# bloodhound_gprs_0_alph.net
KiCad netlist of a schematic drawn in Altium Designer
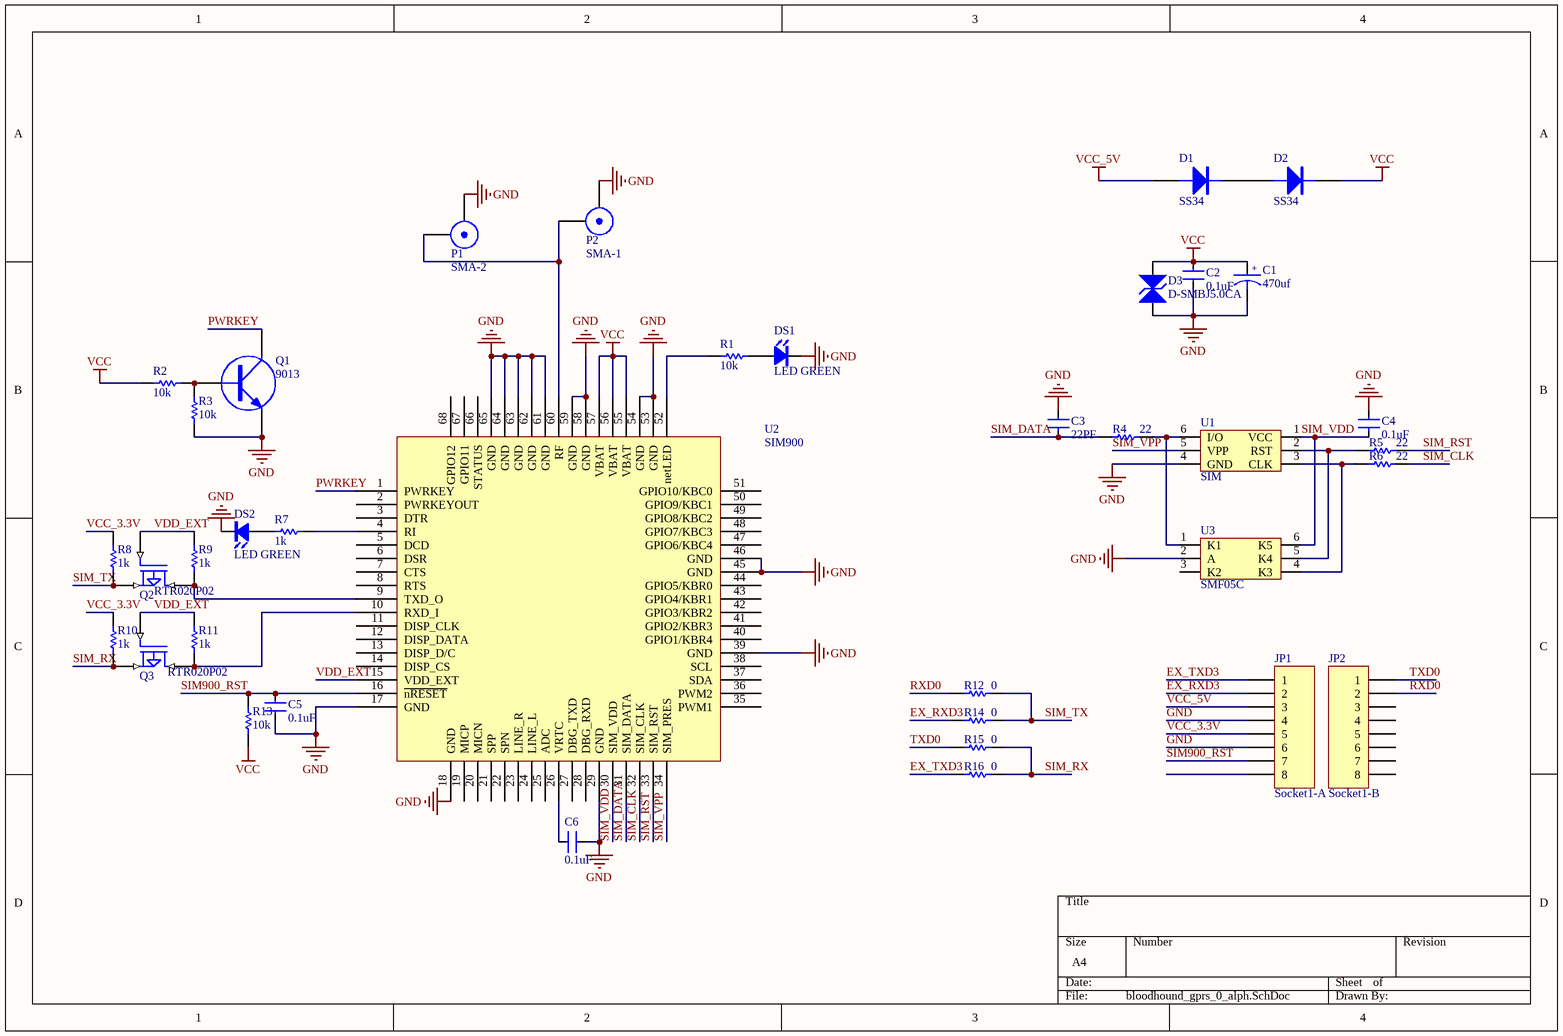
[diagram p0: bloodhound_gprs_0_alph.SchDoc]

(export (version "E")
  (design (tool "Eeschema 10.0.6"))
  (components
    (comp (ref "C1")
      (value "470uf")
      (footprint "C6032")
      (description "钽电容")
      (libsource (lib "BH_DESIGN_DEVICE") (part "CAP-T"))
    )
    (comp (ref "C2")
      (value "0.1uF")
      (footprint "C0603")
      (description "SMD-CAP")
      (libsource (lib "BH_DESIGN_DEVICE") (part "CAP-SMD"))
    )
    (comp (ref "C3")
      (value "22PF")
      (footprint "C0603")
      (description "SMD-CAP")
      (libsource (lib "BH_DESIGN_DEVICE") (part "CAP-SMD"))
    )
    (comp (ref "C4")
      (value "0.1uF")
      (footprint "C0603")
      (description "SMD-CAP")
      (libsource (lib "BH_DESIGN_DEVICE") (part "CAP-SMD"))
    )
    (comp (ref "C5")
      (value "0.1uF")
      (footprint "C0603")
      (description "SMD-CAP")
      (libsource (lib "BH_DESIGN_DEVICE") (part "CAP-SMD"))
    )
    (comp (ref "C6")
      (value "0.1uF")
      (footprint "C0603")
      (description "SMD-CAP")
      (libsource (lib "BH_DESIGN_DEVICE") (part "CAP-SMD"))
    )
    (comp (ref "D1")
      (value "SS34")
      (footprint "DO-214")
      (description "Diode")
      (libsource (lib "BH_DESIGN_DEVICE") (part "DIODE"))
    )
    (comp (ref "D2")
      (value "SS34")
      (footprint "DO-214")
      (description "Diode")
      (libsource (lib "BH_DESIGN_DEVICE") (part "DIODE"))
    )
    (comp (ref "D3")
      (value "D-SMBJ5.0CA")
      (footprint "DO-214")
      (description "TVS")
      (libsource (lib "BH_DESIGN_DEVICE") (part "D-SMBJ5.0CA"))
    )
    (comp (ref "DS1") (value "LED GREEN") (footprint "D0805") (libsource (lib "") (part "LED_1")))
    (comp (ref "DS2")
      (value "LED GREEN")
      (footprint "D0805")
      (libsource (lib "BH_DESIGN_DEVICE") (part "LED"))
    )
    (comp (ref "JP1")
      (value "Socket1-A")
      (footprint "SIP1x8x2.54")
      (description "2.0排针")
      (libsource (lib "5D_CONNECTOR") (part "SIP1X8"))
    )
    (comp (ref "JP2")
      (value "Socket1-B")
      (footprint "SIP1x8x2.54")
      (description "2.0排针")
      (libsource (lib "") (part "SIP1X8_1"))
    )
    (comp (ref "P1")
      (value "SMA-2")
      (footprint "IPX")
      (description "IPX")
      (libsource (lib "BH_DESIGN_CONNECTOR") (part "BNC"))
    )
    (comp (ref "P2")
      (value "SMA-1")
      (footprint "SMA-2")
      (description "SMB-KWE")
      (libsource (lib "") (part "BNC_1"))
    )
    (comp (ref "Q1")
      (value "9013")
      (footprint "SOT23-3L")
      (description "NPN Transistor")
      (libsource (lib "BH_DESIGN_DEVICE") (part "NPN"))
    )
    (comp (ref "Q2")
      (value "RTR020P02")
      (footprint "TSMT3")
      (description "P MOSFET")
      (libsource (lib "BH_DESIGN_DEVICE") (part "MOSFET P"))
    )
    (comp (ref "Q3")
      (value "RTR020P02")
      (footprint "TSMT3")
      (description "P MOSFET")
      (libsource (lib "BH_DESIGN_DEVICE") (part "MOSFET P"))
    )
    (comp (ref "R1")
      (value "10k")
      (footprint "R0603")
      (description "Resistor")
      (libsource (lib "BH_DESIGN_DEVICE") (part "RES"))
    )
    (comp (ref "R2")
      (value "10k")
      (footprint "R0603")
      (description "Resistor")
      (libsource (lib "BH_DESIGN_DEVICE") (part "RES"))
    )
    (comp (ref "R3")
      (value "10k")
      (footprint "R0603")
      (description "Resistor")
      (libsource (lib "BH_DESIGN_DEVICE") (part "RES"))
    )
    (comp (ref "R4")
      (value "22")
      (footprint "R0603")
      (description "Resistor")
      (libsource (lib "BH_DESIGN_DEVICE") (part "RES"))
    )
    (comp (ref "R5")
      (value "22")
      (footprint "R0603")
      (description "Resistor")
      (libsource (lib "BH_DESIGN_DEVICE") (part "RES"))
    )
    (comp (ref "R6")
      (value "22")
      (footprint "R0603")
      (description "Resistor")
      (libsource (lib "BH_DESIGN_DEVICE") (part "RES"))
    )
    (comp (ref "R7")
      (value "1k")
      (footprint "R0603")
      (description "Resistor")
      (libsource (lib "BH_DESIGN_DEVICE") (part "RES"))
    )
    (comp (ref "R8")
      (value "1k")
      (footprint "R0603")
      (description "Resistor")
      (libsource (lib "BH_DESIGN_DEVICE") (part "RES"))
    )
    (comp (ref "R9")
      (value "1k")
      (footprint "R0603")
      (description "Resistor")
      (libsource (lib "BH_DESIGN_DEVICE") (part "RES"))
    )
    (comp (ref "R10")
      (value "1k")
      (footprint "R0603")
      (description "Resistor")
      (libsource (lib "BH_DESIGN_DEVICE") (part "RES"))
    )
    (comp (ref "R11")
      (value "1k")
      (footprint "R0603")
      (description "Resistor")
      (libsource (lib "BH_DESIGN_DEVICE") (part "RES"))
    )
    (comp (ref "R12")
      (value "0")
      (footprint "R0603")
      (description "Resistor")
      (libsource (lib "BH_DESIGN_DEVICE") (part "RES"))
    )
    (comp (ref "R13")
      (value "10k")
      (footprint "R0603")
      (description "Resistor")
      (libsource (lib "BH_DESIGN_DEVICE") (part "RES"))
    )
    (comp (ref "R14")
      (value "0")
      (footprint "R0603")
      (description "Resistor")
      (libsource (lib "BH_DESIGN_DEVICE") (part "RES"))
    )
    (comp (ref "R15")
      (value "0")
      (footprint "R0603")
      (description "Resistor")
      (libsource (lib "BH_DESIGN_DEVICE") (part "RES"))
    )
    (comp (ref "R16")
      (value "0")
      (footprint "R0603")
      (description "Resistor")
      (libsource (lib "BH_DESIGN_DEVICE") (part "RES"))
    )
    (comp (ref "U1")
      (value "SIM")
      (footprint "SIM")
      (description "手机SIM卡")
      (libsource (lib "BH_DESIGN_CONNECTOR") (part "SIM"))
    )
    (comp (ref "U2")
      (value "SIM900")
      (footprint "GSM_900A")
      (libsource (lib "BH_DESIGN_DEVICE") (part "SIM900"))
    )
    (comp (ref "U3")
      (value "SMF05C")
      (footprint "SOT-363")
      (description "TVS")
      (libsource (lib "SIM900_MD") (part "SMF05C"))
    )
  )
  (nets
    (net (code "1") (name "/EX_RXD3") (class "Default")
      (node (ref "JP1") (pin "2") (pinfunction "2_2") (pintype "passive"))
      (node (ref "R14") (pin "2") (pinfunction "2_2") (pintype "passive"))
    )
    (net (code "2") (name "/EX_TXD3") (class "Default")
      (node (ref "JP1") (pin "1") (pinfunction "1_1") (pintype "passive"))
      (node (ref "R16") (pin "2") (pinfunction "2_2") (pintype "passive"))
    )
    (net (code "3") (name "/PWRKEY") (class "Default")
      (node (ref "Q1") (pin "C") (pinfunction "C_C") (pintype "passive"))
      (node (ref "U2") (pin "1") (pinfunction "PWRKEY_1") (pintype "passive"))
    )
    (net (code "4") (name "/RXD0") (class "Default")
      (node (ref "JP2") (pin "2") (pinfunction "2_2") (pintype "passive"))
      (node (ref "R12") (pin "2") (pinfunction "2_2") (pintype "passive"))
    )
    (net (code "5") (name "/SIM900_RST") (class "Default")
      (node (ref "C5") (pin "1") (pinfunction "1_1") (pintype "passive"))
      (node (ref "JP1") (pin "7") (pinfunction "7_7") (pintype "passive"))
      (node (ref "R13") (pin "1") (pinfunction "1_1") (pintype "passive"))
      (node (ref "U2") (pin "16") (pinfunction "~{nRESET}_16") (pintype "passive"))
    )
    (net (code "6") (name "/SIM_CLK") (class "Default")
      (node (ref "R6") (pin "1") (pinfunction "1_1") (pintype "passive"))
      (node (ref "U2") (pin "32") (pinfunction "SIM_CLK_32") (pintype "passive"))
    )
    (net (code "7") (name "/SIM_DATA") (class "Default")
      (node (ref "C3") (pin "1") (pinfunction "1_1") (pintype "passive"))
      (node (ref "R4") (pin "2") (pinfunction "2_2") (pintype "passive"))
      (node (ref "U2") (pin "31") (pinfunction "SIM_DATA_31") (pintype "passive"))
    )
    (net (code "8") (name "/SIM_RST") (class "Default")
      (node (ref "R5") (pin "1") (pinfunction "1_1") (pintype "passive"))
      (node (ref "U2") (pin "33") (pinfunction "SIM_RST_33") (pintype "passive"))
    )
    (net (code "9") (name "/SIM_RX") (class "Default")
      (node (ref "Q3") (pin "3") (pinfunction "S_3") (pintype "input"))
      (node (ref "R10") (pin "2") (pinfunction "2_2") (pintype "passive"))
      (node (ref "R15") (pin "1") (pinfunction "1_1") (pintype "passive"))
      (node (ref "R16") (pin "1") (pinfunction "1_1") (pintype "passive"))
    )
    (net (code "10") (name "/SIM_TX") (class "Default")
      (node (ref "Q2") (pin "3") (pinfunction "S_3") (pintype "input"))
      (node (ref "R12") (pin "1") (pinfunction "1_1") (pintype "passive"))
      (node (ref "R14") (pin "1") (pinfunction "1_1") (pintype "passive"))
      (node (ref "R8") (pin "2") (pinfunction "2_2") (pintype "passive"))
    )
    (net (code "11") (name "/SIM_VDD") (class "Default")
      (node (ref "C4") (pin "1") (pinfunction "1_1") (pintype "passive"))
      (node (ref "U1") (pin "1") (pinfunction "VCC_1") (pintype "passive"))
      (node (ref "U2") (pin "30") (pinfunction "SIM_VDD_30") (pintype "passive"))
      (node (ref "U3") (pin "6") (pinfunction "K5_6") (pintype "passive"))
    )
    (net (code "12") (name "/SIM_VPP") (class "Default")
      (node (ref "U1") (pin "5") (pinfunction "VPP_5") (pintype "passive"))
      (node (ref "U2") (pin "34") (pinfunction "SIM_PRES_34") (pintype "passive"))
    )
    (net (code "13") (name "/TXD0") (class "Default")
      (node (ref "JP2") (pin "1") (pinfunction "1_1") (pintype "passive"))
      (node (ref "R15") (pin "2") (pinfunction "2_2") (pintype "passive"))
    )
    (net (code "14") (name "/VCC_3.3V") (class "Default")
      (node (ref "JP1") (pin "5") (pinfunction "5_5") (pintype "passive"))
      (node (ref "R10") (pin "1") (pinfunction "1_1") (pintype "passive"))
      (node (ref "R8") (pin "1") (pinfunction "1_1") (pintype "passive"))
    )
    (net (code "15") (name "/VDD_EXT") (class "Default")
      (node (ref "Q2") (pin "1") (pinfunction "G_1") (pintype "input"))
      (node (ref "Q3") (pin "1") (pinfunction "G_1") (pintype "input"))
      (node (ref "R11") (pin "1") (pinfunction "1_1") (pintype "passive"))
      (node (ref "R9") (pin "1") (pinfunction "1_1") (pintype "passive"))
      (node (ref "U2") (pin "15") (pinfunction "VDD_EXT_15") (pintype "passive"))
    )
    (net (code "16") (name "GND") (class "Default")
      (node (ref "C1") (pin "2") (pinfunction "2_2") (pintype "passive"))
      (node (ref "C2") (pin "1") (pinfunction "1_1") (pintype "passive"))
      (node (ref "C3") (pin "2") (pinfunction "2_2") (pintype "passive"))
      (node (ref "C4") (pin "2") (pinfunction "2_2") (pintype "passive"))
      (node (ref "C5") (pin "2") (pinfunction "2_2") (pintype "passive"))
      (node (ref "C6") (pin "2") (pinfunction "2_2") (pintype "passive"))
      (node (ref "D3") (pin "A") (pinfunction "1_A") (pintype "passive"))
      (node (ref "DS1") (pin "K") (pinfunction "2_K") (pintype "passive"))
      (node (ref "DS2") (pin "K") (pinfunction "2_K") (pintype "passive"))
      (node (ref "JP1") (pin "4") (pinfunction "4_4") (pintype "passive"))
      (node (ref "JP1") (pin "6") (pinfunction "6_6") (pintype "passive"))
      (node (ref "P1") (pin "2") (pinfunction "Y_2") (pintype "passive"))
      (node (ref "P2") (pin "2") (pinfunction "Y_2") (pintype "passive"))
      (node (ref "Q1") (pin "E") (pinfunction "E_E") (pintype "passive"))
      (node (ref "R3") (pin "1") (pinfunction "1_1") (pintype "passive"))
      (node (ref "U1") (pin "4") (pinfunction "GND_4") (pintype "passive"))
      (node (ref "U2") (pin "17") (pinfunction "GND_17") (pintype "passive"))
      (node (ref "U2") (pin "18") (pinfunction "GND_18") (pintype "passive"))
      (node (ref "U2") (pin "29") (pinfunction "GND_29") (pintype "passive"))
      (node (ref "U2") (pin "39") (pinfunction "GND_39") (pintype "passive"))
      (node (ref "U2") (pin "45") (pinfunction "GND_45") (pintype "passive"))
      (node (ref "U2") (pin "46") (pinfunction "GND_46") (pintype "passive"))
      (node (ref "U2") (pin "53") (pinfunction "GND_53") (pintype "passive"))
      (node (ref "U2") (pin "54") (pinfunction "GND_54") (pintype "passive"))
      (node (ref "U2") (pin "58") (pinfunction "GND_58") (pintype "passive"))
      (node (ref "U2") (pin "59") (pinfunction "GND_59") (pintype "passive"))
      (node (ref "U2") (pin "61") (pinfunction "GND_61") (pintype "passive"))
      (node (ref "U2") (pin "62") (pinfunction "GND_62") (pintype "passive"))
      (node (ref "U2") (pin "63") (pinfunction "GND_63") (pintype "passive"))
      (node (ref "U2") (pin "64") (pinfunction "GND_64") (pintype "passive"))
      (node (ref "U2") (pin "65") (pinfunction "GND_65") (pintype "passive"))
      (node (ref "U3") (pin "2") (pinfunction "A_2") (pintype "passive"))
    )
    (net (code "17") (name "Net-(D1-K)") (class "Default")
      (node (ref "D1") (pin "2") (pinfunction "K_2") (pintype "passive"))
      (node (ref "D2") (pin "1") (pinfunction "A_1") (pintype "passive"))
    )
    (net (code "18") (name "Net-(DS1-1)") (class "Default")
      (node (ref "DS1") (pin "A") (pinfunction "1_A") (pintype "passive"))
      (node (ref "R1") (pin "1") (pinfunction "1_1") (pintype "passive"))
    )
    (net (code "19") (name "Net-(DS2-1)") (class "Default")
      (node (ref "DS2") (pin "A") (pinfunction "1_A") (pintype "passive"))
      (node (ref "R7") (pin "1") (pinfunction "1_1") (pintype "passive"))
    )
    (net (code "20") (name "Net-(P1-X)") (class "Default")
      (node (ref "P1") (pin "1") (pinfunction "X_1") (pintype "passive"))
      (node (ref "P2") (pin "1") (pinfunction "X_1") (pintype "passive"))
      (node (ref "U2") (pin "60") (pinfunction "RF_60") (pintype "passive"))
    )
    (net (code "21") (name "Net-(Q1-PadB)") (class "Default")
      (node (ref "Q1") (pin "B") (pinfunction "B_B") (pintype "passive"))
      (node (ref "R2") (pin "2") (pinfunction "2_2") (pintype "passive"))
      (node (ref "R3") (pin "2") (pinfunction "2_2") (pintype "passive"))
    )
    (net (code "22") (name "Net-(Q2-D)") (class "Default")
      (node (ref "Q2") (pin "2") (pinfunction "D_2") (pintype "input"))
      (node (ref "R9") (pin "2") (pinfunction "2_2") (pintype "passive"))
      (node (ref "U2") (pin "9") (pinfunction "TXD_O_9") (pintype "passive"))
    )
    (net (code "23") (name "Net-(Q3-D)") (class "Default")
      (node (ref "Q3") (pin "2") (pinfunction "D_2") (pintype "input"))
      (node (ref "R11") (pin "2") (pinfunction "2_2") (pintype "passive"))
      (node (ref "U2") (pin "10") (pinfunction "RXD_I_10") (pintype "passive"))
    )
    (net (code "24") (name "Net-(U1-CLK)") (class "Default")
      (node (ref "R6") (pin "2") (pinfunction "2_2") (pintype "passive"))
      (node (ref "U1") (pin "3") (pinfunction "CLK_3") (pintype "passive"))
      (node (ref "U3") (pin "4") (pinfunction "K3_4") (pintype "passive"))
    )
    (net (code "25") (name "Net-(U1-I{slash}O)") (class "Default")
      (node (ref "R4") (pin "1") (pinfunction "1_1") (pintype "passive"))
      (node (ref "U1") (pin "6") (pinfunction "I/O_6") (pintype "passive"))
      (node (ref "U3") (pin "1") (pinfunction "K1_1") (pintype "passive"))
    )
    (net (code "26") (name "Net-(U1-RST)") (class "Default")
      (node (ref "R5") (pin "2") (pinfunction "2_2") (pintype "passive"))
      (node (ref "U1") (pin "2") (pinfunction "RST_2") (pintype "passive"))
      (node (ref "U3") (pin "5") (pinfunction "K4_5") (pintype "passive"))
    )
    (net (code "27") (name "Net-(U2-RI)") (class "Default")
      (node (ref "R7") (pin "2") (pinfunction "2_2") (pintype "passive"))
      (node (ref "U2") (pin "4") (pinfunction "RI_4") (pintype "passive"))
    )
    (net (code "28") (name "Net-(U2-VRTC)") (class "Default")
      (node (ref "C6") (pin "1") (pinfunction "1_1") (pintype "passive"))
      (node (ref "U2") (pin "26") (pinfunction "VRTC_26") (pintype "passive"))
    )
    (net (code "29") (name "Net-(U2-netLED)") (class "Default")
      (node (ref "R1") (pin "2") (pinfunction "2_2") (pintype "passive"))
      (node (ref "U2") (pin "52") (pinfunction "netLED_52") (pintype "passive"))
    )
    (net (code "30") (name "VCC") (class "Default")
      (node (ref "C1") (pin "1") (pinfunction "1_1") (pintype "passive"))
      (node (ref "C2") (pin "2") (pinfunction "2_2") (pintype "passive"))
      (node (ref "D2") (pin "2") (pinfunction "K_2") (pintype "passive"))
      (node (ref "D3") (pin "K") (pinfunction "2_K") (pintype "passive"))
      (node (ref "R13") (pin "2") (pinfunction "2_2") (pintype "passive"))
      (node (ref "R2") (pin "1") (pinfunction "1_1") (pintype "passive"))
      (node (ref "U2") (pin "55") (pinfunction "VBAT_55") (pintype "passive"))
      (node (ref "U2") (pin "56") (pinfunction "VBAT_56") (pintype "passive"))
      (node (ref "U2") (pin "57") (pinfunction "VBAT_57") (pintype "passive"))
    )
    (net (code "31") (name "VCC_5V") (class "Default")
      (node (ref "D1") (pin "1") (pinfunction "A_1") (pintype "passive"))
      (node (ref "JP1") (pin "3") (pinfunction "3_3") (pintype "passive"))
    )
    (net (code "32") (name "unconnected-(JP1-Pad8)") (class "Default")
      (node (ref "JP1") (pin "8") (pinfunction "8_8") (pintype "passive"))
    )
    (net (code "33") (name "unconnected-(JP2-Pad3)") (class "Default")
      (node (ref "JP2") (pin "3") (pinfunction "3_3") (pintype "passive"))
    )
    (net (code "34") (name "unconnected-(JP2-Pad4)") (class "Default")
      (node (ref "JP2") (pin "4") (pinfunction "4_4") (pintype "passive"))
    )
    (net (code "35") (name "unconnected-(JP2-Pad5)") (class "Default")
      (node (ref "JP2") (pin "5") (pinfunction "5_5") (pintype "passive"))
    )
    (net (code "36") (name "unconnected-(JP2-Pad6)") (class "Default")
      (node (ref "JP2") (pin "6") (pinfunction "6_6") (pintype "passive"))
    )
    (net (code "37") (name "unconnected-(JP2-Pad7)") (class "Default")
      (node (ref "JP2") (pin "7") (pinfunction "7_7") (pintype "passive"))
    )
    (net (code "38") (name "unconnected-(JP2-Pad8)") (class "Default")
      (node (ref "JP2") (pin "8") (pinfunction "8_8") (pintype "passive"))
    )
    (net (code "39") (name "unconnected-(U2-ADC-Pad25)") (class "Default")
      (node (ref "U2") (pin "25") (pinfunction "ADC_25") (pintype "passive"))
    )
    (net (code "40") (name "unconnected-(U2-CTS-Pad7)") (class "Default")
      (node (ref "U2") (pin "7") (pinfunction "CTS_7") (pintype "passive"))
    )
    (net (code "41") (name "unconnected-(U2-DBG_RXD-Pad28)") (class "Default")
      (node (ref "U2") (pin "28") (pinfunction "DBG_RXD_28") (pintype "passive"))
    )
    (net (code "42") (name "unconnected-(U2-DBG_TXD-Pad27)") (class "Default")
      (node (ref "U2") (pin "27") (pinfunction "DBG_TXD_27") (pintype "passive"))
    )
    (net (code "43") (name "unconnected-(U2-DCD-Pad5)") (class "Default")
      (node (ref "U2") (pin "5") (pinfunction "DCD_5") (pintype "passive"))
    )
    (net (code "44") (name "unconnected-(U2-DISP_CLK-Pad11)") (class "Default")
      (node (ref "U2") (pin "11") (pinfunction "DISP_CLK_11") (pintype "passive"))
    )
    (net (code "45") (name "unconnected-(U2-DISP_CS-Pad14)") (class "Default")
      (node (ref "U2") (pin "14") (pinfunction "DISP_CS_14") (pintype "passive"))
    )
    (net (code "46") (name "unconnected-(U2-DISP_DATA-Pad12)") (class "Default")
      (node (ref "U2") (pin "12") (pinfunction "DISP_DATA_12") (pintype "passive"))
    )
    (net (code "47") (name "unconnected-(U2-DISP_D{slash}C-Pad13)") (class "Default")
      (node (ref "U2") (pin "13") (pinfunction "DISP_D/C_13") (pintype "passive"))
    )
    (net (code "48") (name "unconnected-(U2-DSR-Pad6)") (class "Default")
      (node (ref "U2") (pin "6") (pinfunction "DSR_6") (pintype "passive"))
    )
    (net (code "49") (name "unconnected-(U2-DTR-Pad3)") (class "Default")
      (node (ref "U2") (pin "3") (pinfunction "DTR_3") (pintype "passive"))
    )
    (net (code "50") (name "unconnected-(U2-GPIO1{slash}KBR4-Pad40)") (class "Default")
      (node (ref "U2") (pin "40") (pinfunction "GPIO1/KBR4_40") (pintype "passive"))
    )
    (net (code "51") (name "unconnected-(U2-GPIO2{slash}KBR3-Pad41)") (class "Default")
      (node (ref "U2") (pin "41") (pinfunction "GPIO2/KBR3_41") (pintype "passive"))
    )
    (net (code "52") (name "unconnected-(U2-GPIO3{slash}KBR2-Pad42)") (class "Default")
      (node (ref "U2") (pin "42") (pinfunction "GPIO3/KBR2_42") (pintype "passive"))
    )
    (net (code "53") (name "unconnected-(U2-GPIO4{slash}KBR1-Pad43)") (class "Default")
      (node (ref "U2") (pin "43") (pinfunction "GPIO4/KBR1_43") (pintype "passive"))
    )
    (net (code "54") (name "unconnected-(U2-GPIO5{slash}KBR0-Pad44)") (class "Default")
      (node (ref "U2") (pin "44") (pinfunction "GPIO5/KBR0_44") (pintype "passive"))
    )
    (net (code "55") (name "unconnected-(U2-GPIO6{slash}KBC4-Pad47)") (class "Default")
      (node (ref "U2") (pin "47") (pinfunction "GPIO6/KBC4_47") (pintype "passive"))
    )
    (net (code "56") (name "unconnected-(U2-GPIO7{slash}KBC3-Pad48)") (class "Default")
      (node (ref "U2") (pin "48") (pinfunction "GPIO7/KBC3_48") (pintype "passive"))
    )
    (net (code "57") (name "unconnected-(U2-GPIO8{slash}KBC2-Pad49)") (class "Default")
      (node (ref "U2") (pin "49") (pinfunction "GPIO8/KBC2_49") (pintype "passive"))
    )
    (net (code "58") (name "unconnected-(U2-GPIO9{slash}KBC1-Pad50)") (class "Default")
      (node (ref "U2") (pin "50") (pinfunction "GPIO9/KBC1_50") (pintype "passive"))
    )
    (net (code "59") (name "unconnected-(U2-GPIO10{slash}KBC0-Pad51)") (class "Default")
      (node (ref "U2") (pin "51") (pinfunction "GPIO10/KBC0_51") (pintype "passive"))
    )
    (net (code "60") (name "unconnected-(U2-GPIO11-Pad67)") (class "Default")
      (node (ref "U2") (pin "67") (pinfunction "GPIO11_67") (pintype "passive"))
    )
    (net (code "61") (name "unconnected-(U2-GPIO12-Pad68)") (class "Default")
      (node (ref "U2") (pin "68") (pinfunction "GPIO12_68") (pintype "passive"))
    )
    (net (code "62") (name "unconnected-(U2-LINE_L-Pad24)") (class "Default")
      (node (ref "U2") (pin "24") (pinfunction "LINE_L_24") (pintype "passive"))
    )
    (net (code "63") (name "unconnected-(U2-LINE_R-Pad23)") (class "Default")
      (node (ref "U2") (pin "23") (pinfunction "LINE_R_23") (pintype "passive"))
    )
    (net (code "64") (name "unconnected-(U2-MICN-Pad20)") (class "Default")
      (node (ref "U2") (pin "20") (pinfunction "MICN_20") (pintype "passive"))
    )
    (net (code "65") (name "unconnected-(U2-MICP-Pad19)") (class "Default")
      (node (ref "U2") (pin "19") (pinfunction "MICP_19") (pintype "passive"))
    )
    (net (code "66") (name "unconnected-(U2-PWM1-Pad35)") (class "Default")
      (node (ref "U2") (pin "35") (pinfunction "PWM1_35") (pintype "passive"))
    )
    (net (code "67") (name "unconnected-(U2-PWM2-Pad36)") (class "Default")
      (node (ref "U2") (pin "36") (pinfunction "PWM2_36") (pintype "passive"))
    )
    (net (code "68") (name "unconnected-(U2-PWRKEYOUT-Pad2)") (class "Default")
      (node (ref "U2") (pin "2") (pinfunction "PWRKEYOUT_2") (pintype "passive"))
    )
    (net (code "69") (name "unconnected-(U2-RTS-Pad8)") (class "Default")
      (node (ref "U2") (pin "8") (pinfunction "RTS_8") (pintype "passive"))
    )
    (net (code "70") (name "unconnected-(U2-SCL-Pad38)") (class "Default")
      (node (ref "U2") (pin "38") (pinfunction "SCL_38") (pintype "passive"))
    )
    (net (code "71") (name "unconnected-(U2-SDA-Pad37)") (class "Default")
      (node (ref "U2") (pin "37") (pinfunction "SDA_37") (pintype "passive"))
    )
    (net (code "72") (name "unconnected-(U2-SPN-Pad22)") (class "Default")
      (node (ref "U2") (pin "22") (pinfunction "SPN_22") (pintype "passive"))
    )
    (net (code "73") (name "unconnected-(U2-SPP-Pad21)") (class "Default")
      (node (ref "U2") (pin "21") (pinfunction "SPP_21") (pintype "passive"))
    )
    (net (code "74") (name "unconnected-(U2-STATUS-Pad66)") (class "Default")
      (node (ref "U2") (pin "66") (pinfunction "STATUS_66") (pintype "passive"))
    )
    (net (code "75") (name "unconnected-(U3-K2-Pad3)") (class "Default")
      (node (ref "U3") (pin "3") (pinfunction "K2_3") (pintype "passive"))
    )
  )
)
